# 8_oledDisplay.net
KiCad netlist of a schematic drawn in Altium Designer
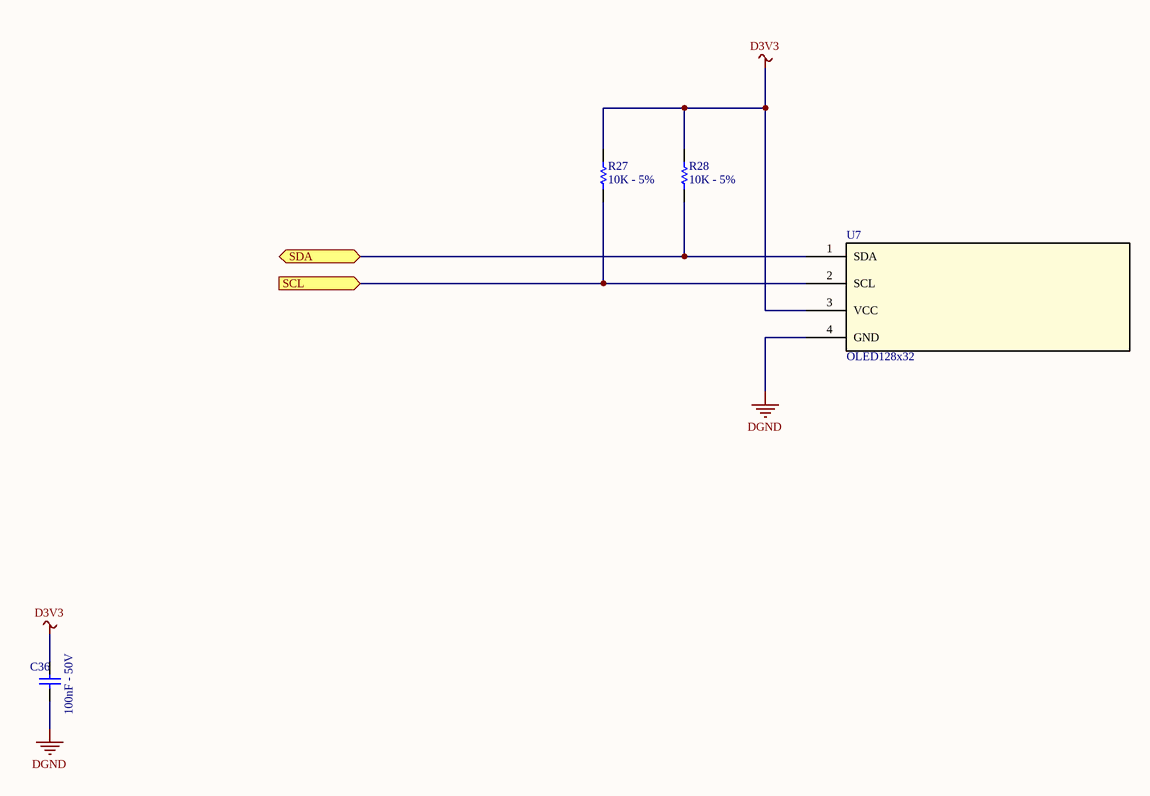
[diagram p0: 8_oledDisplay.SchDoc]

(export (version "E")
  (design (tool "Eeschema 10.0.6"))
  (components
    (comp (ref "C36")
      (value "Capacitor 100 nF - 10%")
      (footprint "SMD0805-CAP")
      (description "Capacitor 100nF, 10%, SMD 0805")
      (fields
        (field (name "MANUFACTURER") "AVX")
        (field (name "PARTNUMBER") "08055C104KAT2A")
        (field (name "VALOR") "100nF - 50V")
      )
      (libsource (lib "Capacitor_smd") (part "100nF - 50V - 10% - 0805 - 580"))
    )
    (comp (ref "R27")
      (value "10K - 5% - 0805 - 328")
      (footprint "SMD0805")
      (description "Resistor 10K, 5%, SMD 0805")
      (fields
        (field (name "PARTNUMBER") "RC2012J103CS")
        (field (name "MANUFACTURER") "SAMSUNG")
        (field (name "VALOR") "10K - 5%")
      )
      (libsource (lib "Resistor_smd") (part "10K - 5% - 0805 - 328"))
    )
    (comp (ref "R28")
      (value "10K - 5% - 0805 - 328")
      (footprint "SMD0805")
      (description "Resistor 10K, 5%, SMD 0805")
      (fields
        (field (name "PARTNUMBER") "RC2012J103CS")
        (field (name "MANUFACTURER") "SAMSUNG")
        (field (name "VALOR") "10K - 5%")
      )
      (libsource (lib "Resistor_smd") (part "10K - 5% - 0805 - 328"))
    )
    (comp (ref "U7")
      (value "OLED128x32")
      (footprint "SGTL5000XNAA3:OLEDGREATZT128x32")
      (libsource (lib "SGTL5000XNAA3") (part "OLED128x32"))
    )
  )
  (nets
    (net (code "1") (name "/SCL") (class "Default")
      (node (ref "R27") (pin "1") (pinfunction "1_1") (pintype "passive"))
      (node (ref "U7") (pin "2") (pinfunction "SCL_2") (pintype "passive"))
    )
    (net (code "2") (name "/SDA") (class "Default")
      (node (ref "R28") (pin "1") (pinfunction "1_1") (pintype "passive"))
      (node (ref "U7") (pin "1") (pinfunction "SDA_1") (pintype "passive"))
    )
    (net (code "3") (name "D3V3") (class "Default")
      (node (ref "C36") (pin "1") (pinfunction "1_1") (pintype "passive"))
      (node (ref "R27") (pin "2") (pinfunction "2_2") (pintype "passive"))
      (node (ref "R28") (pin "2") (pinfunction "2_2") (pintype "passive"))
      (node (ref "U7") (pin "3") (pinfunction "VCC_3") (pintype "power_in"))
    )
    (net (code "4") (name "DGND") (class "Default")
      (node (ref "C36") (pin "2") (pinfunction "2_2") (pintype "passive"))
      (node (ref "U7") (pin "4") (pinfunction "GND_4") (pintype "power_in"))
    )
  )
)
